# BMS_Master_RevC2.net
KiCad netlist of a schematic drawn in EAGLE
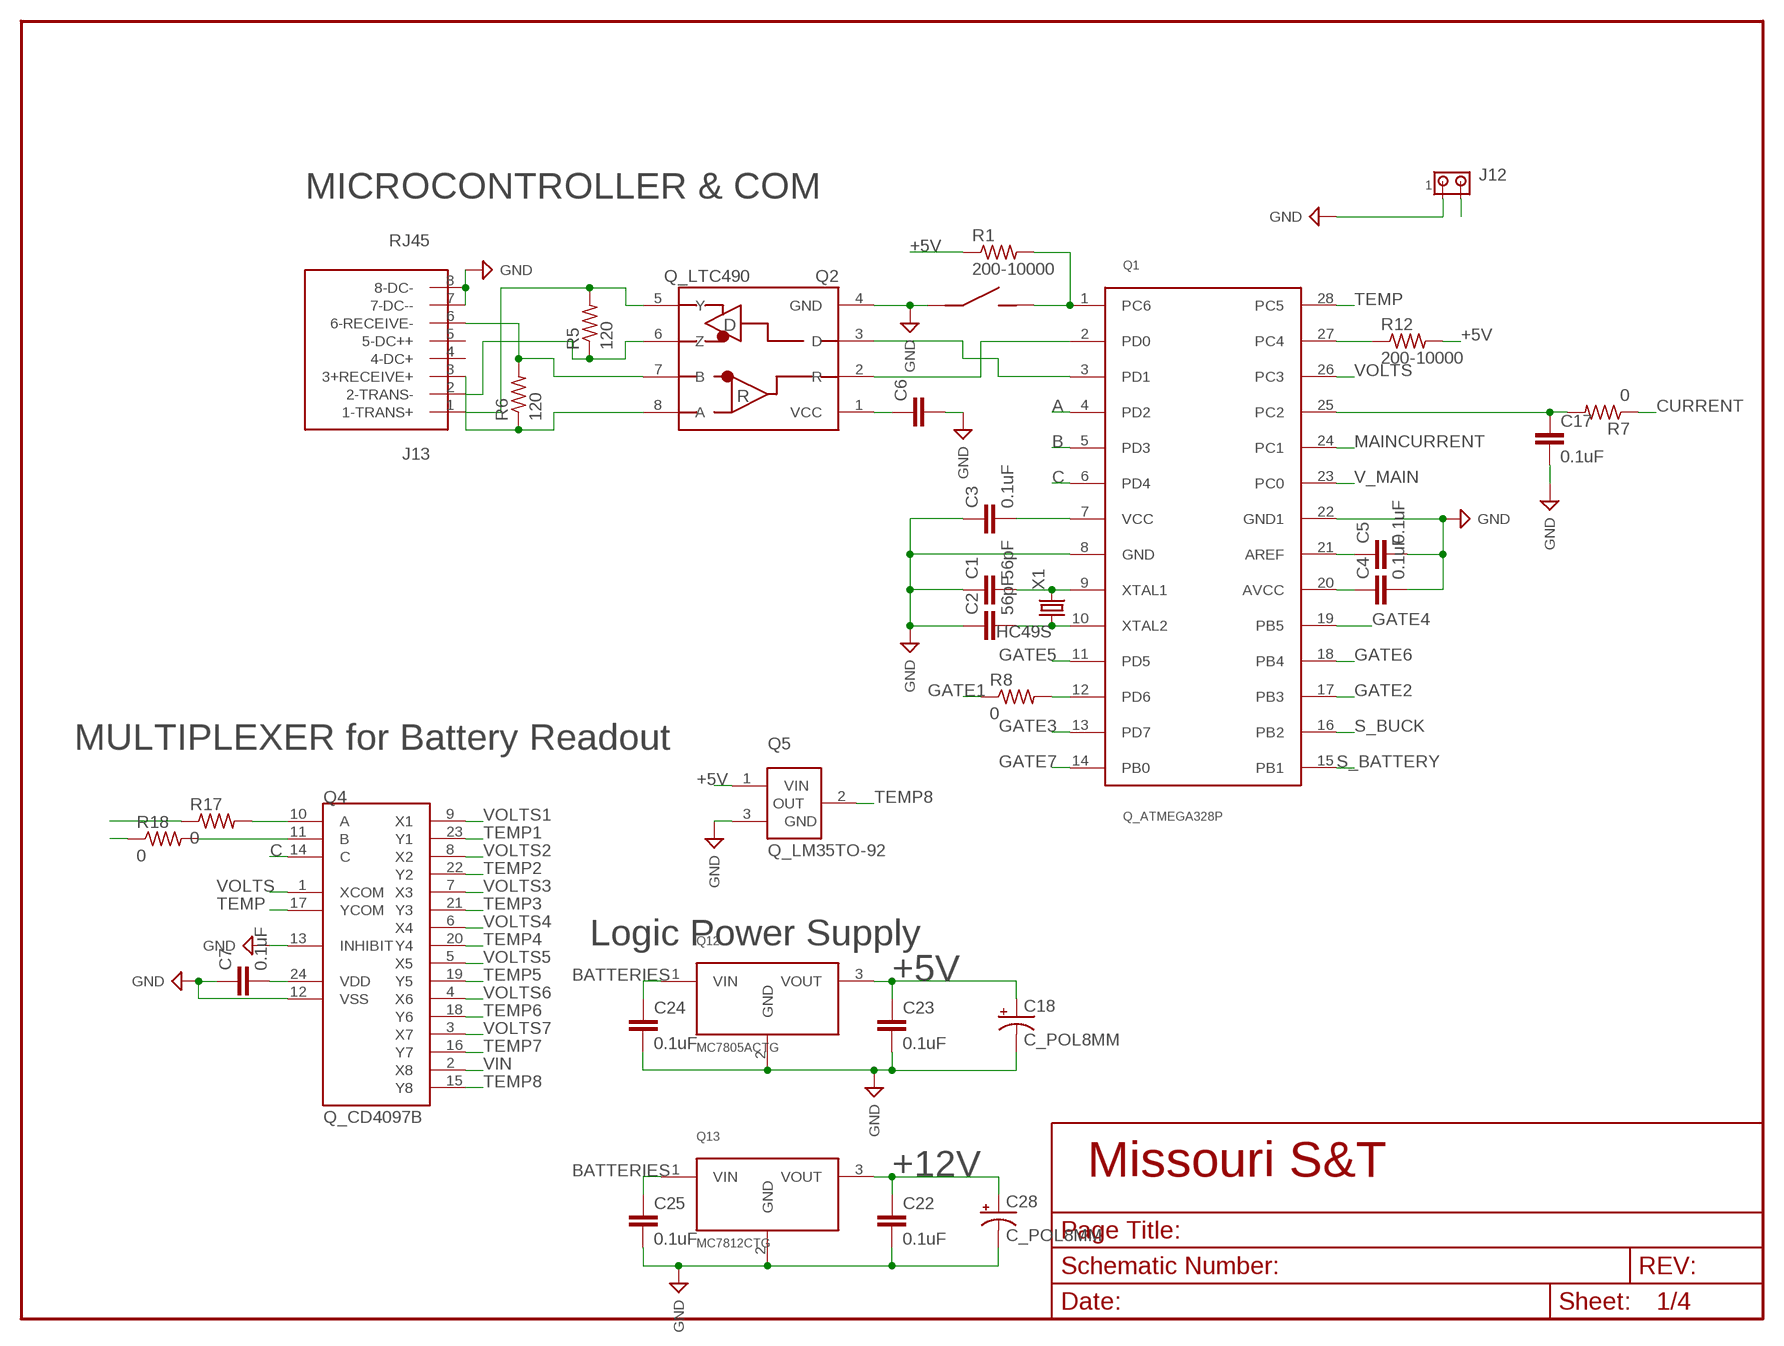
[diagram p0: schematic, sheet 1]
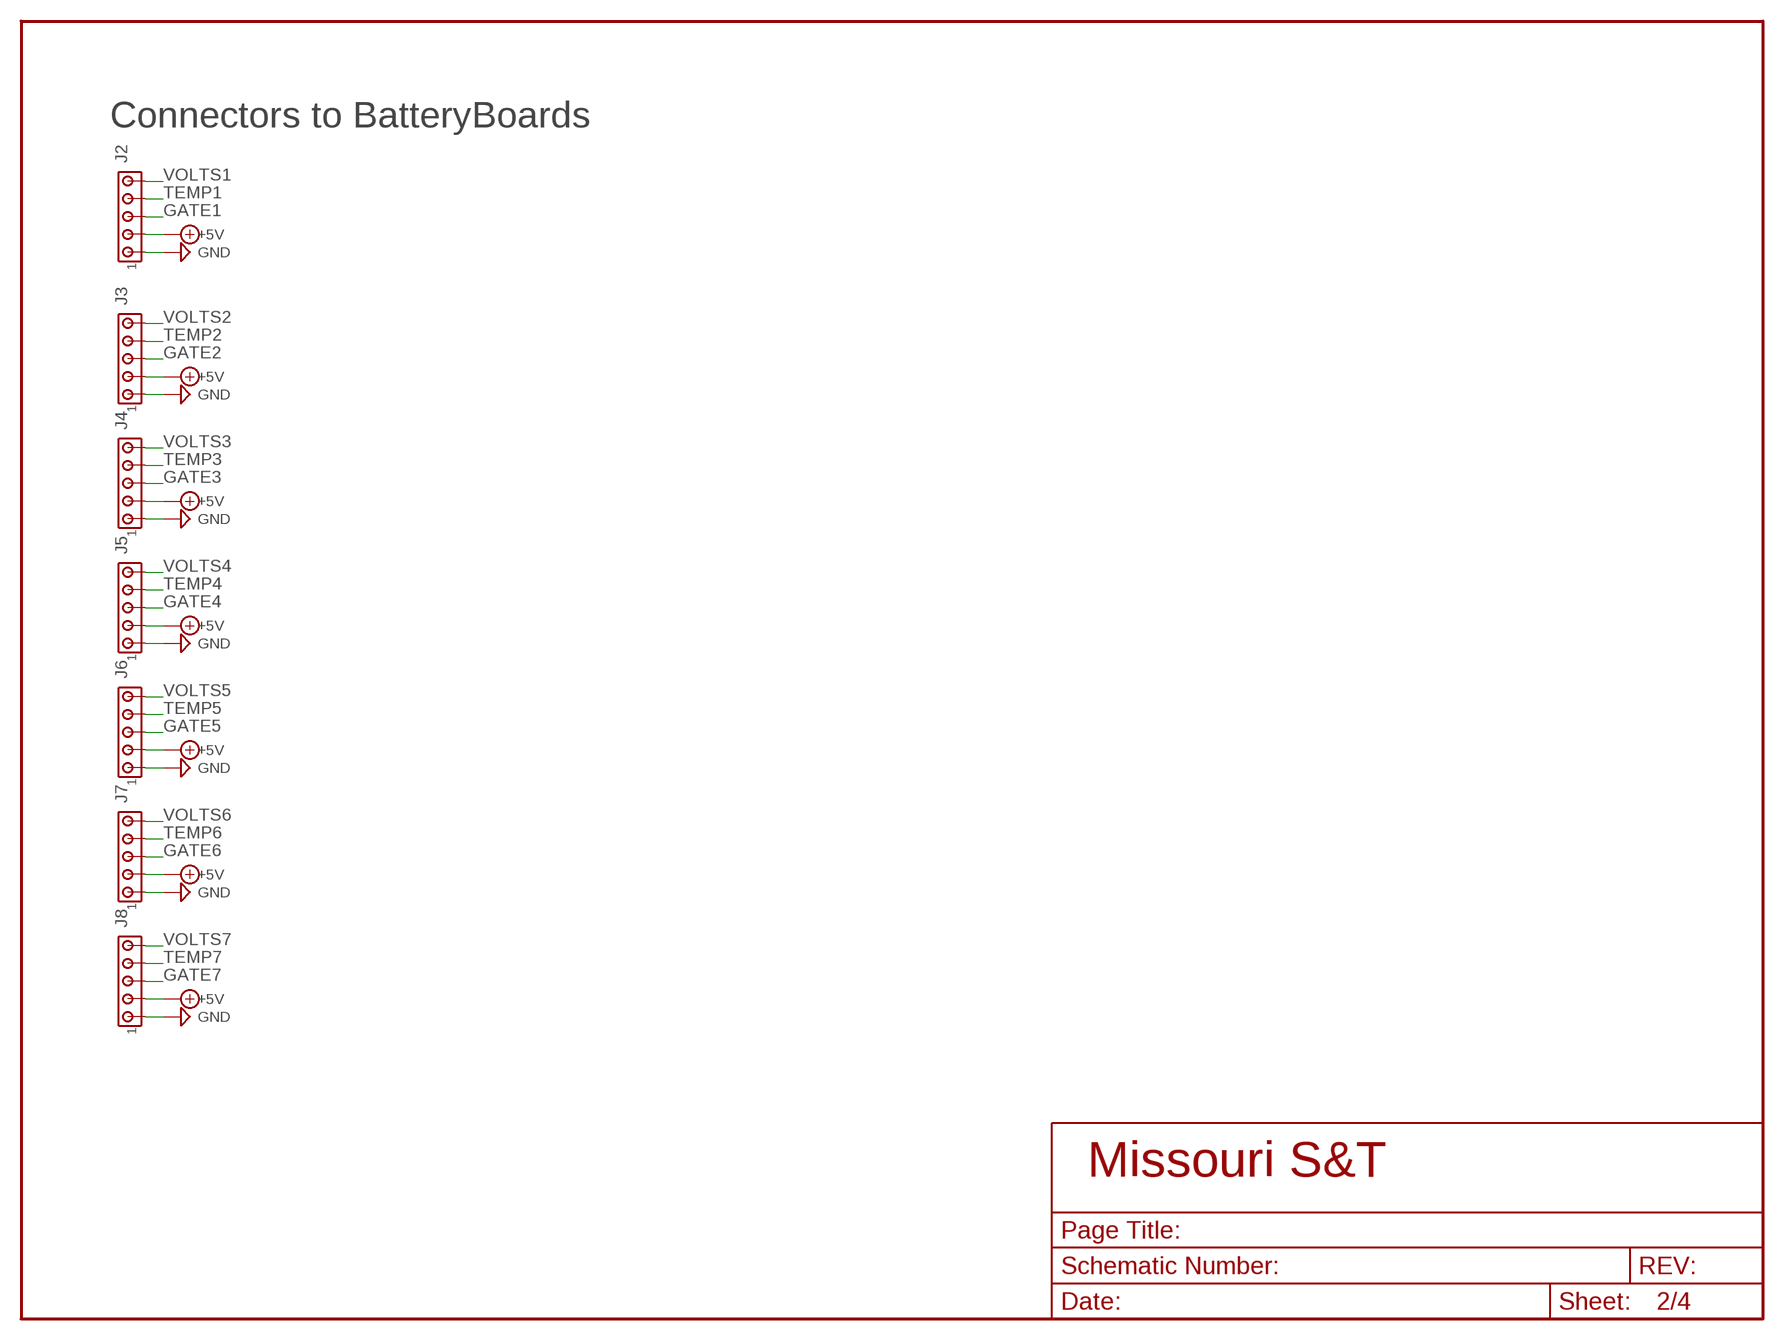
[diagram p1: schematic, sheet 2]
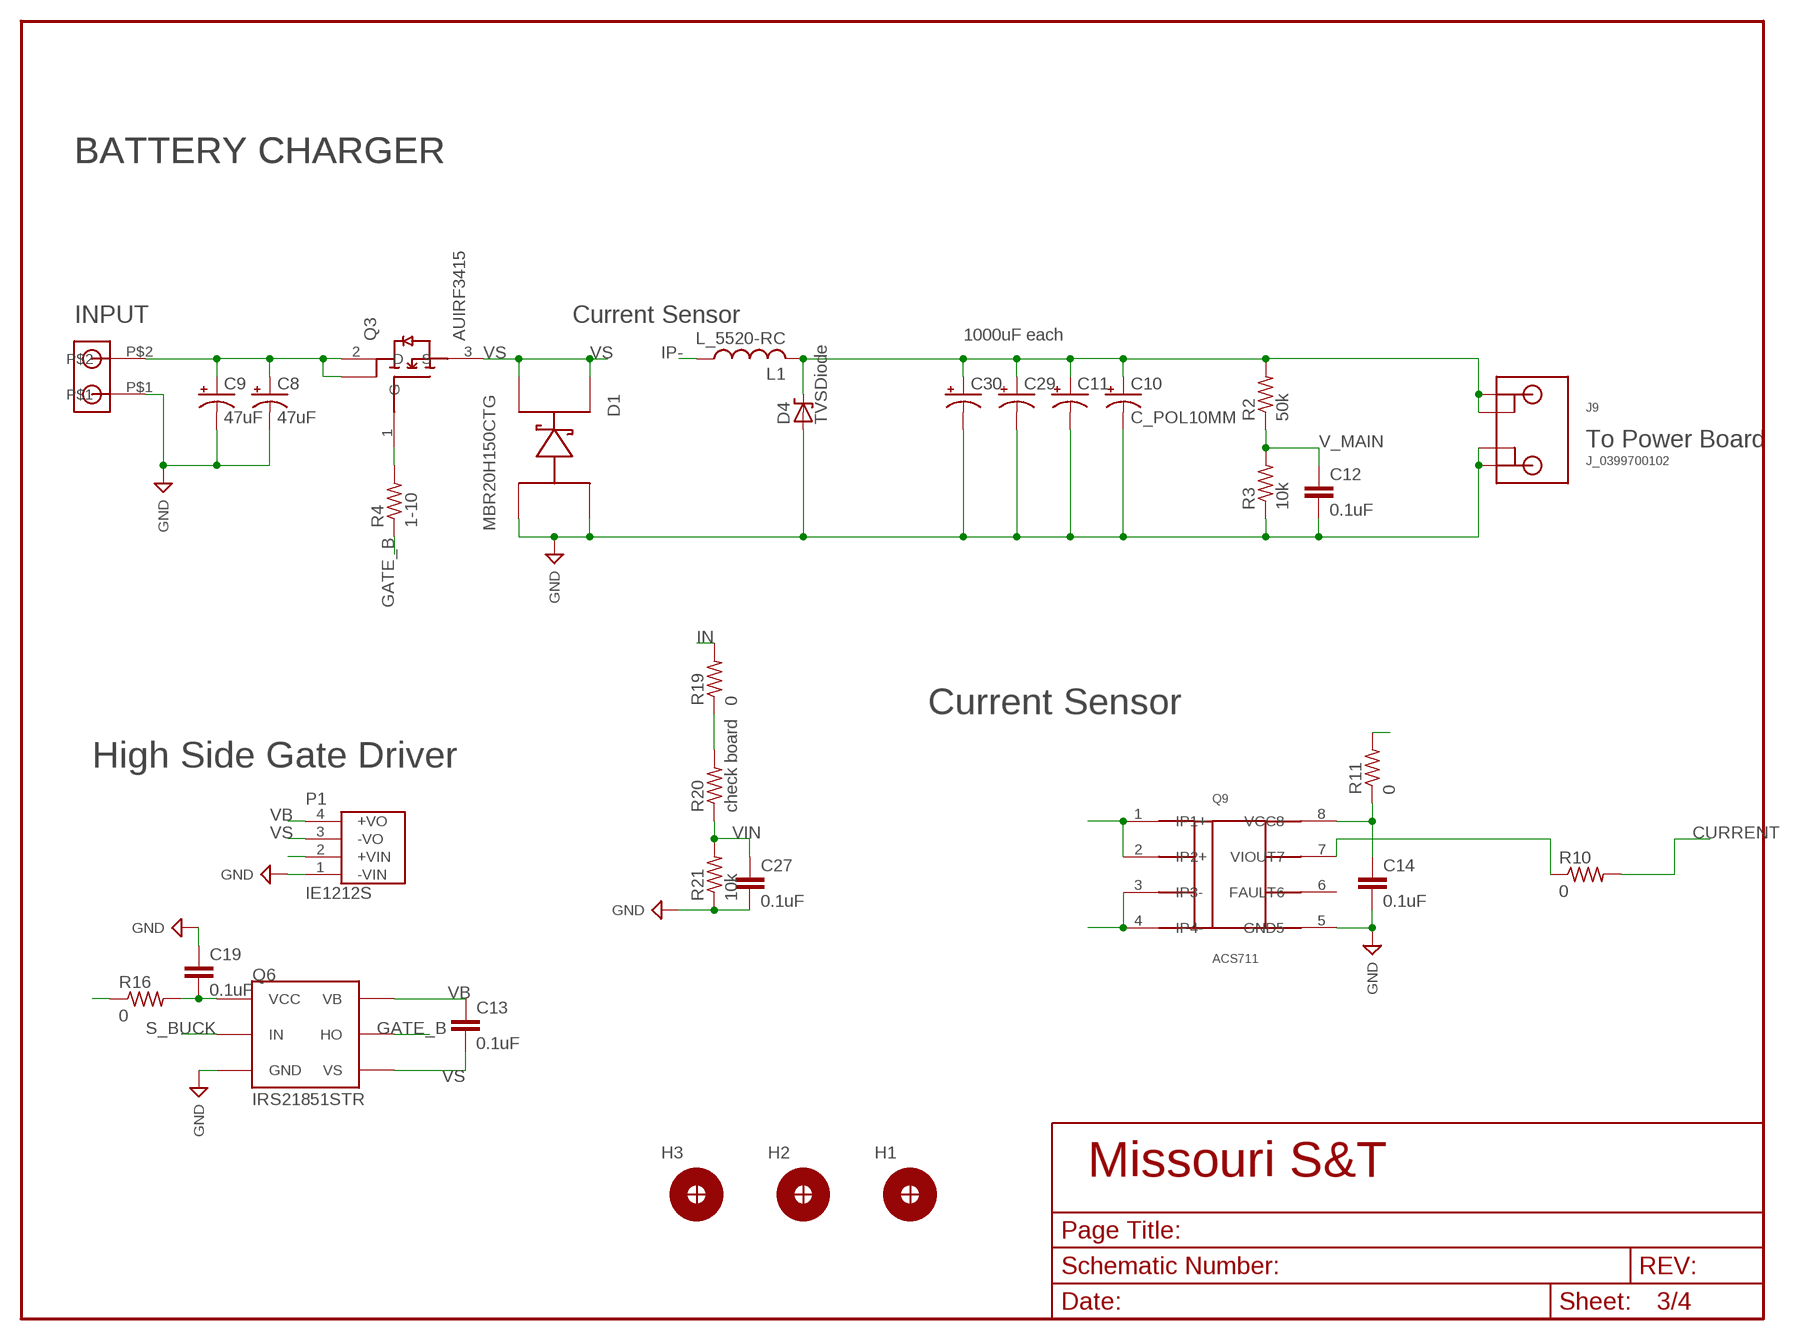
[diagram p2: schematic, sheet 3]
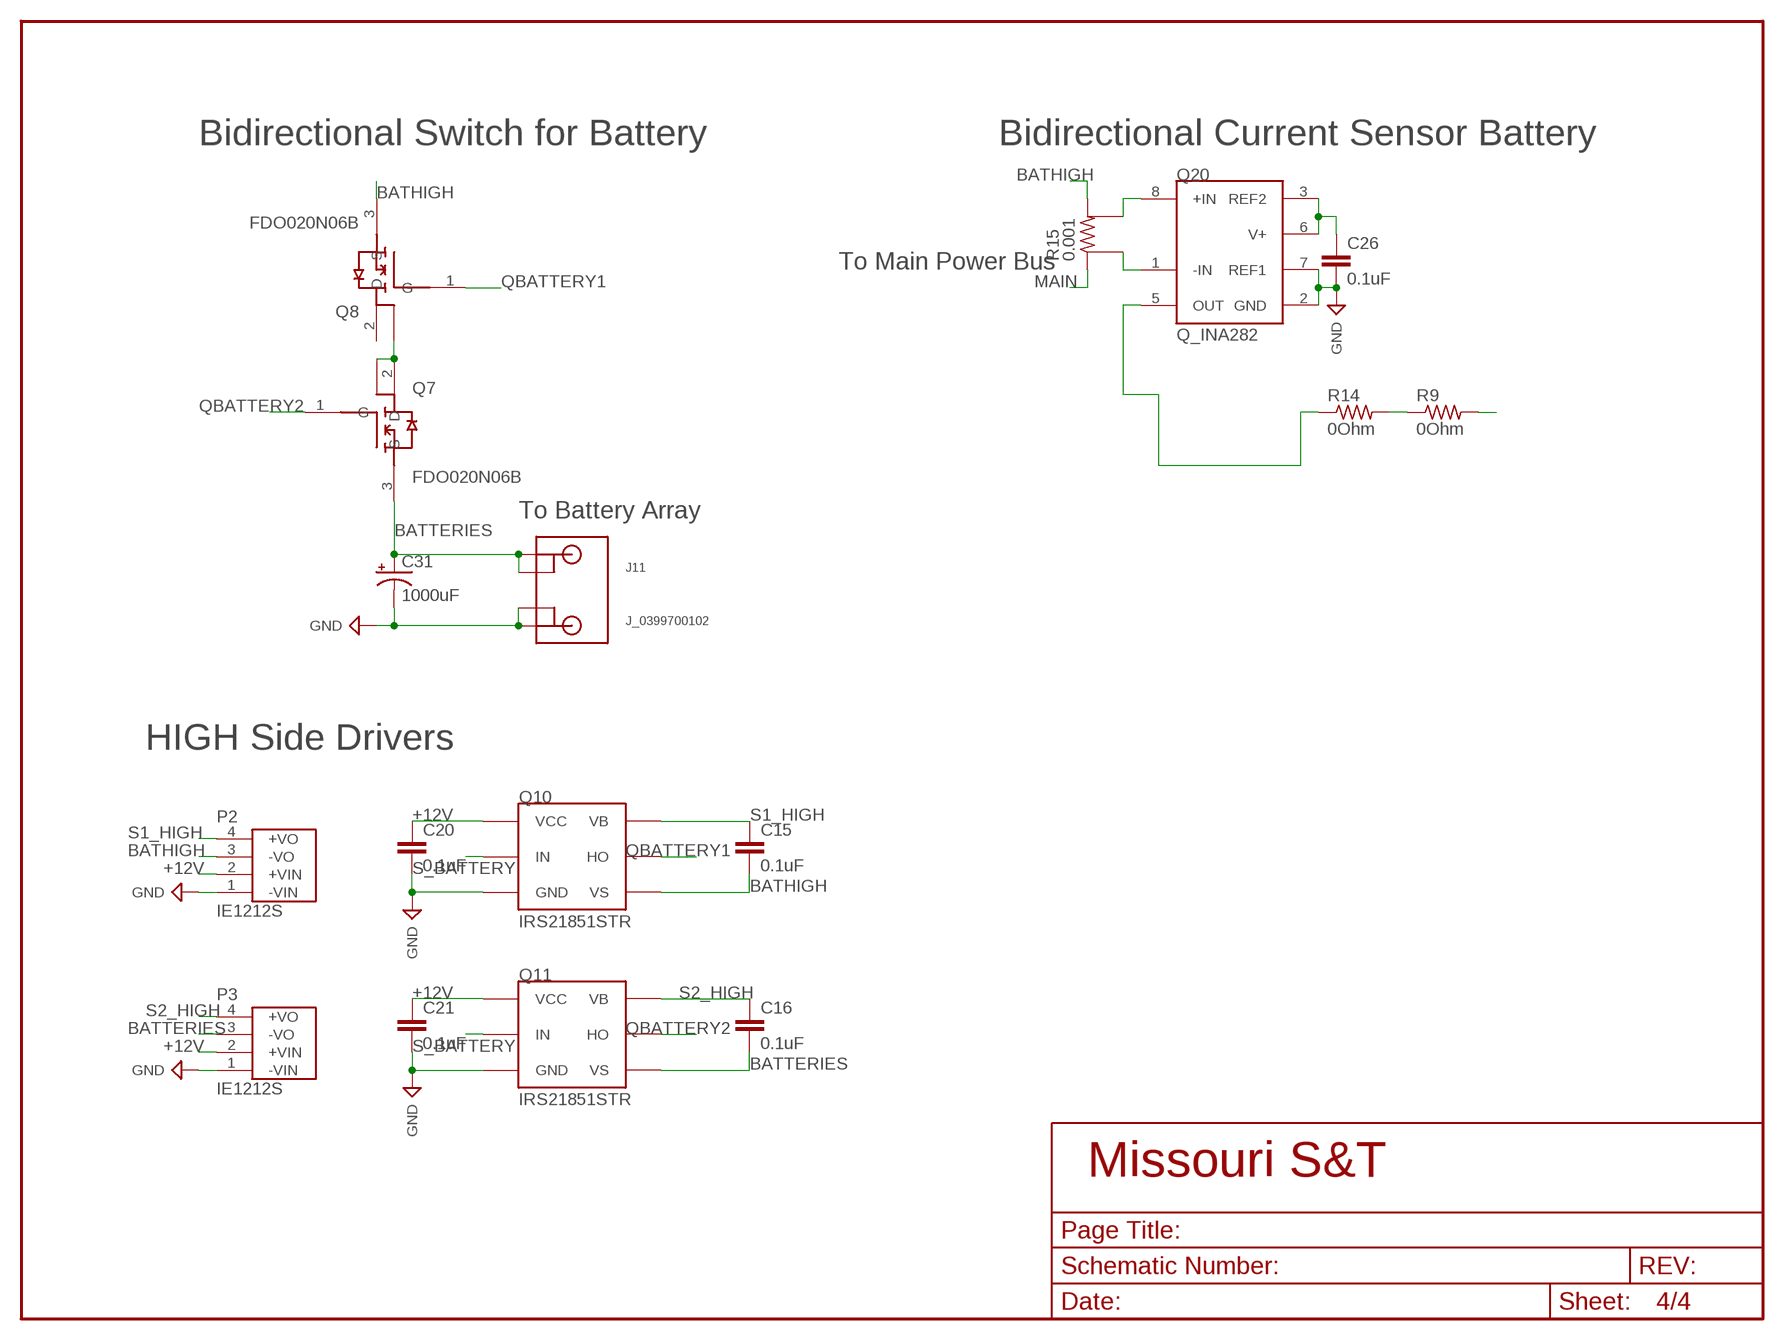
[diagram p3: schematic, sheet 4]

(export (version "E")
  (design (tool "Eeschema 10.0.6"))
  (components
    (comp (ref "J2")
      (value "J_MTA5P_100")
      (footprint "eagle-import:J_MTA100_5P")
      (libsource (lib "eagle-import") (part "J_MTA5P_100"))
    )
    (comp (ref "J3")
      (value "J_MTA5P_100")
      (footprint "eagle-import:J_MTA100_5P")
      (libsource (lib "eagle-import") (part "J_MTA5P_100"))
    )
    (comp (ref "J4")
      (value "J_MTA5P_100")
      (footprint "eagle-import:J_MTA100_5P")
      (libsource (lib "eagle-import") (part "J_MTA5P_100"))
    )
    (comp (ref "J5")
      (value "J_MTA5P_100")
      (footprint "eagle-import:J_MTA100_5P")
      (libsource (lib "eagle-import") (part "J_MTA5P_100"))
    )
    (comp (ref "J6")
      (value "J_MTA5P_100")
      (footprint "eagle-import:J_MTA100_5P")
      (libsource (lib "eagle-import") (part "J_MTA5P_100"))
    )
    (comp (ref "J7")
      (value "J_MTA5P_100")
      (footprint "eagle-import:J_MTA100_5P")
      (libsource (lib "eagle-import") (part "J_MTA5P_100"))
    )
    (comp (ref "J8")
      (value "J_MTA5P_100")
      (footprint "eagle-import:J_MTA100_5P")
      (libsource (lib "eagle-import") (part "J_MTA5P_100"))
    )
    (comp (ref "C8")
      (value "47uF")
      (footprint "eagle-import:C_10MM")
      (libsource (lib "eagle-import") (part "C_POL10MM"))
    )
    (comp (ref "C9")
      (value "47uF")
      (footprint "eagle-import:C_10MM")
      (libsource (lib "eagle-import") (part "C_POL10MM"))
    )
    (comp (ref "C10")
      (value "C_POL10MM")
      (footprint "eagle-import:C_10MM")
      (libsource (lib "eagle-import") (part "C_POL10MM"))
    )
    (comp (ref "C11")
      (value "C_POL10MM")
      (footprint "eagle-import:C_10MM")
      (libsource (lib "eagle-import") (part "C_POL10MM"))
    )
    (comp (ref "C12")
      (value "0.1uF")
      (footprint "eagle-import:C_1206")
      (libsource (lib "eagle-import") (part "C_CAP_1206"))
    )
    (comp (ref "C13")
      (value "0.1uF")
      (footprint "eagle-import:C_1206")
      (libsource (lib "eagle-import") (part "C_CAP_1206"))
    )
    (comp (ref "C14")
      (value "0.1uF")
      (footprint "eagle-import:C_1206")
      (libsource (lib "eagle-import") (part "C_CAP_1206"))
    )
    (comp (ref "C19")
      (value "0.1uF")
      (footprint "eagle-import:C_1206")
      (libsource (lib "eagle-import") (part "C_CAP_1206"))
    )
    (comp (ref "C27")
      (value "0.1uF")
      (footprint "eagle-import:C_1206")
      (libsource (lib "eagle-import") (part "C_CAP_1206"))
    )
    (comp (ref "C29")
      (value "C_POL10MM")
      (footprint "eagle-import:C_10MM")
      (libsource (lib "eagle-import") (part "C_POL10MM"))
    )
    (comp (ref "C30")
      (value "C_POL10MM")
      (footprint "eagle-import:C_10MM")
      (libsource (lib "eagle-import") (part "C_POL10MM"))
    )
    (comp (ref "D1")
      (value "MBR20H150CTG")
      (footprint "eagle-import:TO-220-FLAT")
      (libsource (lib "eagle-import") (part "D_MBR20H150CTG"))
    )
    (comp (ref "D4")
      (value "TVSDiode")
      (footprint "eagle-import:DIODE_D3.5MM_LS15.24MM")
      (libsource (lib "eagle-import") (part "D_1.5KE480A_D3.5MM_LS15.24MM"))
    )
    (comp (ref "H1")
      (value "H_MNTHOLE_#6")
      (footprint "eagle-import:H_MNTHOLE_#6")
      (libsource (lib "eagle-import") (part "H_MNTHOLE_#6"))
    )
    (comp (ref "H2")
      (value "H_MNTHOLE_#6")
      (footprint "eagle-import:H_MNTHOLE_#6")
      (libsource (lib "eagle-import") (part "H_MNTHOLE_#6"))
    )
    (comp (ref "H3")
      (value "H_MNTHOLE_#6")
      (footprint "eagle-import:H_MNTHOLE_#6")
      (libsource (lib "eagle-import") (part "H_MNTHOLE_#6"))
    )
    (comp (ref "J9")
      (value "J_0399700102")
      (footprint "eagle-import:J_2CONHC")
      (libsource (lib "eagle-import") (part "J_0399700102"))
    )
    (comp (ref "J10")
      (value "J_1546074-2")
      (footprint "eagle-import:THERM_BLOCK_2")
      (libsource (lib "eagle-import") (part "J_1546074-2"))
    )
    (comp (ref "L1")
      (value "L_5520-RC")
      (footprint "eagle-import:L_5520-RC")
      (libsource (lib "eagle-import") (part "L_5520-RC"))
    )
    (comp (ref "P1")
      (value "IE1212S")
      (footprint "eagle-import:TME1215S")
      (libsource (lib "eagle-import") (part "TME1215S"))
    )
    (comp (ref "Q3")
      (value "AUIRF3415")
      (footprint "eagle-import:TO-220-FLAT")
      (libsource (lib "eagle-import") (part "Q_CSD18532KCSPCB"))
    )
    (comp (ref "Q6")
      (value "IRS21851STR")
      (footprint "eagle-import:SOIC8")
      (libsource (lib "eagle-import") (part "Q_IRS21851STR"))
    )
    (comp (ref "Q9")
      (value "ACS711")
      (footprint "eagle-import:Q_SO8")
      (libsource (lib "eagle-import") (part "Q_SO8ACS711"))
    )
    (comp (ref "R2")
      (value "50k")
      (footprint "eagle-import:R_1_4W")
      (libsource (lib "eagle-import") (part "R_1/4W"))
    )
    (comp (ref "R3")
      (value "10k")
      (footprint "eagle-import:R_1206")
      (libsource (lib "eagle-import") (part "R_RES_1206"))
    )
    (comp (ref "R4")
      (value "1-10")
      (footprint "eagle-import:R_1206")
      (libsource (lib "eagle-import") (part "Lib_Passive - Copy_R_RES_1206"))
    )
    (comp (ref "R10")
      (value "0")
      (footprint "eagle-import:R_1_4W")
      (libsource (lib "eagle-import") (part "R_1/4W"))
    )
    (comp (ref "R11")
      (value "0")
      (footprint "eagle-import:R_1_4W")
      (libsource (lib "eagle-import") (part "R_1/4W"))
    )
    (comp (ref "R16")
      (value "0")
      (footprint "eagle-import:R_1_4W")
      (libsource (lib "eagle-import") (part "R_1/4W"))
    )
    (comp (ref "R19")
      (value "0")
      (footprint "eagle-import:R_1_4W")
      (libsource (lib "eagle-import") (part "R_1/4W"))
    )
    (comp (ref "R20")
      (value "check board")
      (footprint "eagle-import:R_1_4W")
      (libsource (lib "eagle-import") (part "R_1/4W"))
    )
    (comp (ref "R21")
      (value "10k")
      (footprint "eagle-import:R_1206")
      (libsource (lib "eagle-import") (part "R_RES_1206"))
    )
    (comp (ref "C1")
      (value "56pF")
      (footprint "eagle-import:C_1206")
      (libsource (lib "eagle-import") (part "C_CAP_1206"))
    )
    (comp (ref "C2")
      (value "56pF")
      (footprint "eagle-import:C_1206")
      (libsource (lib "eagle-import") (part "C_CAP_1206"))
    )
    (comp (ref "C3")
      (value "0.1uF")
      (footprint "eagle-import:C_1206")
      (libsource (lib "eagle-import") (part "C_CAP_1206"))
    )
    (comp (ref "C4")
      (value "0.1uF")
      (footprint "eagle-import:C_1206")
      (libsource (lib "eagle-import") (part "C_CAP_1206"))
    )
    (comp (ref "C5")
      (value "0.1uF")
      (footprint "eagle-import:C_1206")
      (libsource (lib "eagle-import") (part "C_CAP_1206"))
    )
    (comp (ref "C6")
      (value "C_CAP_1206")
      (footprint "eagle-import:C_1206")
      (libsource (lib "eagle-import") (part "C_CAP_1206"))
    )
    (comp (ref "C7")
      (value "0.1uF")
      (footprint "eagle-import:C_1206")
      (libsource (lib "eagle-import") (part "C_CAP_1206"))
    )
    (comp (ref "C17")
      (value "0.1uF")
      (footprint "eagle-import:C_1206")
      (libsource (lib "eagle-import") (part "C_CAP_1206"))
    )
    (comp (ref "C18")
      (value "C_POL8MM")
      (footprint "eagle-import:C_8MM")
      (libsource (lib "eagle-import") (part "C_POL8MM"))
    )
    (comp (ref "C22")
      (value "0.1uF")
      (footprint "eagle-import:C_1206")
      (libsource (lib "eagle-import") (part "C_CAP_1206"))
    )
    (comp (ref "C23")
      (value "0.1uF")
      (footprint "eagle-import:C_1206")
      (libsource (lib "eagle-import") (part "C_CAP_1206"))
    )
    (comp (ref "C24")
      (value "0.1uF")
      (footprint "eagle-import:C_1206")
      (libsource (lib "eagle-import") (part "C_CAP_1206"))
    )
    (comp (ref "C25")
      (value "0.1uF")
      (footprint "eagle-import:C_1206")
      (libsource (lib "eagle-import") (part "C_CAP_1206"))
    )
    (comp (ref "C28")
      (value "C_POL8MM")
      (footprint "eagle-import:C_8MM")
      (libsource (lib "eagle-import") (part "C_POL8MM"))
    )
    (comp (ref "J1")
      (value "J_MC32857")
      (footprint "eagle-import:J_TOGGLE")
      (libsource (lib "eagle-import") (part "J_MC32857"))
    )
    (comp (ref "J12")
      (value "J_MTA2P_100")
      (footprint "eagle-import:J_MTA100_2P")
      (libsource (lib "eagle-import") (part "J_MTA2P_100"))
    )
    (comp (ref "J13")
      (value "RJ45")
      (footprint "eagle-import:RJ45-CAT5E")
      (libsource (lib "eagle-import") (part "RJ45"))
    )
    (comp (ref "Q1")
      (value "Q_ATMEGA328P")
      (footprint "eagle-import:DIP28")
      (libsource (lib "eagle-import") (part "Q_ATMEGA328P"))
    )
    (comp (ref "Q2")
      (value "Q_LTC490")
      (footprint "eagle-import:DIP8")
      (libsource (lib "eagle-import") (part "Q_LTC490"))
    )
    (comp (ref "Q4")
      (value "Q_CD4097B")
      (footprint "eagle-import:WDIP24")
      (libsource (lib "eagle-import") (part "Q_CD4067BRIGHT"))
    )
    (comp (ref "Q5")
      (value "Q_LM35TO-92")
      (footprint "eagle-import:TO-92-3")
      (libsource (lib "eagle-import") (part "Q_LM35TO-92"))
    )
    (comp (ref "Q12")
      (value "MC7805ACTG")
      (footprint "eagle-import:TO-220")
      (libsource (lib "eagle-import") (part "Q_LDO"))
    )
    (comp (ref "Q13")
      (value "MC7812CTG")
      (footprint "eagle-import:TO-220")
      (libsource (lib "eagle-import") (part "Q_LDO"))
    )
    (comp (ref "R1")
      (value "200-10000")
      (footprint "eagle-import:R_1206")
      (libsource (lib "eagle-import") (part "R_RES_1206"))
    )
    (comp (ref "R5")
      (value "120")
      (footprint "eagle-import:R_1206")
      (libsource (lib "eagle-import") (part "Lib_Passive - Copy_R_RES_1206"))
    )
    (comp (ref "R6")
      (value "120")
      (footprint "eagle-import:R_1206")
      (libsource (lib "eagle-import") (part "Lib_Passive - Copy_R_RES_1206"))
    )
    (comp (ref "R7")
      (value "0")
      (footprint "eagle-import:R_1_4W")
      (libsource (lib "eagle-import") (part "R_1/4W"))
    )
    (comp (ref "R8")
      (value "0")
      (footprint "eagle-import:R_1_4W")
      (libsource (lib "eagle-import") (part "R_1/4W"))
    )
    (comp (ref "R12")
      (value "200-10000")
      (footprint "eagle-import:R_0805")
      (libsource (lib "eagle-import") (part "R_RES_0805"))
    )
    (comp (ref "R17")
      (value "0")
      (footprint "eagle-import:R_1_4W")
      (libsource (lib "eagle-import") (part "R_1/4W"))
    )
    (comp (ref "R18")
      (value "0")
      (footprint "eagle-import:R_1_4W")
      (libsource (lib "eagle-import") (part "R_1/4W"))
    )
    (comp (ref "X1")
      (value "HC49S")
      (footprint "eagle-import:HC-49")
      (libsource (lib "eagle-import") (part "X_HC49SCRYSTAL"))
    )
    (comp (ref "C15")
      (value "0.1uF")
      (footprint "eagle-import:C_1206")
      (libsource (lib "eagle-import") (part "C_CAP_1206"))
    )
    (comp (ref "C16")
      (value "0.1uF")
      (footprint "eagle-import:C_1206")
      (libsource (lib "eagle-import") (part "C_CAP_1206"))
    )
    (comp (ref "C20")
      (value "0.1uF")
      (footprint "eagle-import:C_1206")
      (libsource (lib "eagle-import") (part "C_CAP_1206"))
    )
    (comp (ref "C21")
      (value "0.1uF")
      (footprint "eagle-import:C_1206")
      (libsource (lib "eagle-import") (part "C_CAP_1206"))
    )
    (comp (ref "C26")
      (value "0.1uF")
      (footprint "eagle-import:C_1206")
      (libsource (lib "eagle-import") (part "C_CAP_1206"))
    )
    (comp (ref "C31")
      (value "1000uF")
      (footprint "eagle-import:C_10MM")
      (libsource (lib "eagle-import") (part "C_POL10MM"))
    )
    (comp (ref "J11")
      (value "J_0399700102")
      (footprint "eagle-import:J_2CONHC")
      (libsource (lib "eagle-import") (part "J_0399700102"))
    )
    (comp (ref "P2")
      (value "IE1212S")
      (footprint "eagle-import:TME1215S")
      (libsource (lib "eagle-import") (part "TME1215S"))
    )
    (comp (ref "P3")
      (value "IE1212S")
      (footprint "eagle-import:TME1215S")
      (libsource (lib "eagle-import") (part "TME1215S"))
    )
    (comp (ref "Q7")
      (value "FDO020N06B")
      (footprint "eagle-import:TO-220-FLAT")
      (libsource (lib "eagle-import") (part "Q_CSD18532KCSPCB"))
    )
    (comp (ref "Q8")
      (value "FDO020N06B")
      (footprint "eagle-import:TO-220-FLAT")
      (libsource (lib "eagle-import") (part "Q_CSD18532KCSPCB"))
    )
    (comp (ref "Q10")
      (value "IRS21851STR")
      (footprint "eagle-import:SOIC8")
      (libsource (lib "eagle-import") (part "Q_IRS21851STR"))
    )
    (comp (ref "Q11")
      (value "IRS21851STR")
      (footprint "eagle-import:SOIC8")
      (libsource (lib "eagle-import") (part "Q_IRS21851STR"))
    )
    (comp (ref "Q20")
      (value "Q_INA282")
      (footprint "eagle-import:SOIC8")
      (libsource (lib "eagle-import") (part "Q_INA28"))
    )
    (comp (ref "R9")
      (value "0Ohm")
      (footprint "eagle-import:R_1_4W")
      (libsource (lib "eagle-import") (part "R_1/4W"))
    )
    (comp (ref "R14")
      (value "0Ohm")
      (footprint "eagle-import:R_1_4W")
      (libsource (lib "eagle-import") (part "R_1/4W"))
    )
    (comp (ref "R15")
      (value "0.001")
      (footprint "eagle-import:R_FC4L")
      (libsource (lib "eagle-import") (part "R_FC4L110R001JER"))
    )
  )
  (nets
    (net (code "1") (name "+5V") (class "Default")
      (node (ref "C18") (pin "+") (pinfunction "+_+") (pintype "passive"))
      (node (ref "C23") (pin "1") (pinfunction "1_1") (pintype "passive"))
      (node (ref "C3") (pin "2") (pinfunction "2_2") (pintype "passive"))
      (node (ref "C4") (pin "1") (pinfunction "1_1") (pintype "passive"))
      (node (ref "C6") (pin "1") (pinfunction "1_1") (pintype "passive"))
      (node (ref "C7") (pin "2") (pinfunction "2_2") (pintype "passive"))
      (node (ref "J2") (pin "2") (pinfunction "2_2") (pintype "passive"))
      (node (ref "J3") (pin "2") (pinfunction "2_2") (pintype "passive"))
      (node (ref "J4") (pin "2") (pinfunction "2_2") (pintype "passive"))
      (node (ref "J5") (pin "2") (pinfunction "2_2") (pintype "passive"))
      (node (ref "J6") (pin "2") (pinfunction "2_2") (pintype "passive"))
      (node (ref "J7") (pin "2") (pinfunction "2_2") (pintype "passive"))
      (node (ref "J8") (pin "2") (pinfunction "2_2") (pintype "passive"))
      (node (ref "Q1") (pin "20") (pinfunction "AVCC_20") (pintype "bidirectional"))
      (node (ref "Q1") (pin "7") (pinfunction "VCC_7") (pintype "bidirectional"))
      (node (ref "Q12") (pin "3") (pinfunction "VOUT_3") (pintype "bidirectional"))
      (node (ref "Q2") (pin "1") (pinfunction "VCC_1") (pintype "bidirectional"))
      (node (ref "Q4") (pin "24") (pinfunction "VDD_24") (pintype "bidirectional"))
      (node (ref "Q5") (pin "1") (pinfunction "VIN_1") (pintype "bidirectional"))
      (node (ref "R1") (pin "1") (pinfunction "1_1") (pintype "passive"))
      (node (ref "R11") (pin "2") (pinfunction "2_2") (pintype "passive"))
      (node (ref "R12") (pin "2") (pinfunction "2_2") (pintype "passive"))
    )
    (net (code "2") (name "+5V1") (class "Default")
      (node (ref "C14") (pin "1") (pinfunction "1_1") (pintype "passive"))
      (node (ref "C26") (pin "1") (pinfunction "1_1") (pintype "passive"))
      (node (ref "Q20") (pin "3") (pinfunction "REF2_3") (pintype "bidirectional"))
      (node (ref "Q20") (pin "6") (pinfunction "V+_6") (pintype "bidirectional"))
      (node (ref "Q9") (pin "8") (pinfunction "VCC8_8") (pintype "bidirectional"))
      (node (ref "R11") (pin "1") (pinfunction "1_1") (pintype "passive"))
    )
    (net (code "3") (name "+12V") (class "Default")
      (node (ref "C20") (pin "1") (pinfunction "1_1") (pintype "passive"))
      (node (ref "C21") (pin "1") (pinfunction "1_1") (pintype "passive"))
      (node (ref "C22") (pin "1") (pinfunction "1_1") (pintype "passive"))
      (node (ref "C28") (pin "+") (pinfunction "+_+") (pintype "passive"))
      (node (ref "P2") (pin "2") (pinfunction "+VIN_2") (pintype "input"))
      (node (ref "P3") (pin "2") (pinfunction "+VIN_2") (pintype "input"))
      (node (ref "Q10") (pin "1") (pinfunction "VCC_1") (pintype "bidirectional"))
      (node (ref "Q11") (pin "1") (pinfunction "VCC_1") (pintype "bidirectional"))
      (node (ref "Q13") (pin "3") (pinfunction "VOUT_3") (pintype "bidirectional"))
      (node (ref "R16") (pin "1") (pinfunction "1_1") (pintype "passive"))
    )
    (net (code "4") (name "+12V1") (class "Default")
      (node (ref "C19") (pin "2") (pinfunction "2_2") (pintype "passive"))
      (node (ref "P1") (pin "2") (pinfunction "+VIN_2") (pintype "input"))
      (node (ref "Q6") (pin "1") (pinfunction "VCC_1") (pintype "bidirectional"))
      (node (ref "R16") (pin "2") (pinfunction "2_2") (pintype "passive"))
    )
    (net (code "5") (name "A") (class "Default")
      (node (ref "Q1") (pin "4") (pinfunction "PD2_4") (pintype "bidirectional"))
      (node (ref "R17") (pin "1") (pinfunction "1_1") (pintype "passive"))
    )
    (net (code "6") (name "B") (class "Default")
      (node (ref "Q1") (pin "5") (pinfunction "PD3_5") (pintype "bidirectional"))
      (node (ref "R18") (pin "1") (pinfunction "1_1") (pintype "passive"))
    )
    (net (code "7") (name "BATHIGH") (class "Default")
      (node (ref "C15") (pin "2") (pinfunction "2_2") (pintype "passive"))
      (node (ref "P2") (pin "3") (pinfunction "-VO_3") (pintype "output"))
      (node (ref "Q10") (pin "6") (pinfunction "VS_6") (pintype "bidirectional"))
      (node (ref "Q8") (pin "3") (pinfunction "S_3") (pintype "bidirectional"))
      (node (ref "R15") (pin "2") (pinfunction "2_2") (pintype "passive"))
    )
    (net (code "8") (name "BATTERIES") (class "Default")
      (node (ref "C16") (pin "2") (pinfunction "2_2") (pintype "passive"))
      (node (ref "C24") (pin "1") (pinfunction "1_1") (pintype "passive"))
      (node (ref "C25") (pin "1") (pinfunction "1_1") (pintype "passive"))
      (node (ref "C31") (pin "P$1") (pinfunction "+_P$1") (pintype "passive"))
      (node (ref "J11") (pin "PIN1-1") (pinfunction "1-1_PIN1-1") (pintype "bidirectional"))
      (node (ref "J11") (pin "PIN1-2") (pinfunction "1-2_PIN1-2") (pintype "bidirectional"))
      (node (ref "P3") (pin "3") (pinfunction "-VO_3") (pintype "output"))
      (node (ref "Q11") (pin "6") (pinfunction "VS_6") (pintype "bidirectional"))
      (node (ref "Q12") (pin "1") (pinfunction "VIN_1") (pintype "bidirectional"))
      (node (ref "Q13") (pin "1") (pinfunction "VIN_1") (pintype "bidirectional"))
      (node (ref "Q7") (pin "3") (pinfunction "S_3") (pintype "bidirectional"))
    )
    (net (code "9") (name "C") (class "Default")
      (node (ref "Q1") (pin "6") (pinfunction "PD4_6") (pintype "bidirectional"))
      (node (ref "Q4") (pin "14") (pinfunction "C_14") (pintype "bidirectional"))
    )
    (net (code "10") (name "CURRENT") (class "Default")
      (node (ref "R10") (pin "2") (pinfunction "2_2") (pintype "passive"))
      (node (ref "R7") (pin "1") (pinfunction "1_1") (pintype "passive"))
    )
    (net (code "11") (name "GATE1") (class "Default")
      (node (ref "J2") (pin "3") (pinfunction "3_3") (pintype "passive"))
      (node (ref "R8") (pin "1") (pinfunction "1_1") (pintype "passive"))
    )
    (net (code "12") (name "GATE2") (class "Default")
      (node (ref "J3") (pin "3") (pinfunction "3_3") (pintype "passive"))
      (node (ref "Q1") (pin "17") (pinfunction "PB3_17") (pintype "bidirectional"))
    )
    (net (code "13") (name "GATE3") (class "Default")
      (node (ref "J4") (pin "3") (pinfunction "3_3") (pintype "passive"))
      (node (ref "Q1") (pin "13") (pinfunction "PD7_13") (pintype "bidirectional"))
    )
    (net (code "14") (name "GATE4") (class "Default")
      (node (ref "J5") (pin "3") (pinfunction "3_3") (pintype "passive"))
      (node (ref "Q1") (pin "19") (pinfunction "PB5_19") (pintype "bidirectional"))
    )
    (net (code "15") (name "GATE5") (class "Default")
      (node (ref "J6") (pin "3") (pinfunction "3_3") (pintype "passive"))
      (node (ref "Q1") (pin "11") (pinfunction "PD5_11") (pintype "bidirectional"))
    )
    (net (code "16") (name "GATE6") (class "Default")
      (node (ref "J7") (pin "3") (pinfunction "3_3") (pintype "passive"))
      (node (ref "Q1") (pin "18") (pinfunction "PB4_18") (pintype "bidirectional"))
    )
    (net (code "17") (name "GATE7") (class "Default")
      (node (ref "J8") (pin "3") (pinfunction "3_3") (pintype "passive"))
      (node (ref "Q1") (pin "14") (pinfunction "PB0_14") (pintype "bidirectional"))
    )
    (net (code "18") (name "GATE_B") (class "Default")
      (node (ref "Q6") (pin "7") (pinfunction "HO_7") (pintype "bidirectional"))
      (node (ref "R4") (pin "1") (pinfunction "1_1") (pintype "passive"))
    )
    (net (code "19") (name "GND") (class "Default")
      (node (ref "C1") (pin "1") (pinfunction "1_1") (pintype "passive"))
      (node (ref "C10") (pin "P$2") (pinfunction "-_P$2") (pintype "passive"))
      (node (ref "C11") (pin "P$2") (pinfunction "-_P$2") (pintype "passive"))
      (node (ref "C12") (pin "2") (pinfunction "2_2") (pintype "passive"))
      (node (ref "C14") (pin "2") (pinfunction "2_2") (pintype "passive"))
      (node (ref "C17") (pin "2") (pinfunction "2_2") (pintype "passive"))
      (node (ref "C18") (pin "-") (pinfunction "-_-") (pintype "passive"))
      (node (ref "C19") (pin "1") (pinfunction "1_1") (pintype "passive"))
      (node (ref "C2") (pin "1") (pinfunction "1_1") (pintype "passive"))
      (node (ref "C20") (pin "2") (pinfunction "2_2") (pintype "passive"))
      (node (ref "C21") (pin "2") (pinfunction "2_2") (pintype "passive"))
      (node (ref "C22") (pin "2") (pinfunction "2_2") (pintype "passive"))
      (node (ref "C23") (pin "2") (pinfunction "2_2") (pintype "passive"))
      (node (ref "C24") (pin "2") (pinfunction "2_2") (pintype "passive"))
      (node (ref "C25") (pin "2") (pinfunction "2_2") (pintype "passive"))
      (node (ref "C26") (pin "2") (pinfunction "2_2") (pintype "passive"))
      (node (ref "C27") (pin "2") (pinfunction "2_2") (pintype "passive"))
      (node (ref "C28") (pin "-") (pinfunction "-_-") (pintype "passive"))
      (node (ref "C29") (pin "P$2") (pinfunction "-_P$2") (pintype "passive"))
      (node (ref "C3") (pin "1") (pinfunction "1_1") (pintype "passive"))
      (node (ref "C30") (pin "P$2") (pinfunction "-_P$2") (pintype "passive"))
      (node (ref "C31") (pin "P$2") (pinfunction "-_P$2") (pintype "passive"))
      (node (ref "C4") (pin "2") (pinfunction "2_2") (pintype "passive"))
      (node (ref "C5") (pin "2") (pinfunction "2_2") (pintype "passive"))
      (node (ref "C6") (pin "2") (pinfunction "2_2") (pintype "passive"))
      (node (ref "C7") (pin "1") (pinfunction "1_1") (pintype "passive"))
      (node (ref "C8") (pin "P$2") (pinfunction "-_P$2") (pintype "passive"))
      (node (ref "C9") (pin "P$2") (pinfunction "-_P$2") (pintype "passive"))
      (node (ref "D1") (pin "1") (pinfunction "A1_1") (pintype "bidirectional"))
      (node (ref "D1") (pin "3") (pinfunction "A2_3") (pintype "bidirectional"))
      (node (ref "D4") (pin "A") (pinfunction "A_A") (pintype "passive"))
      (node (ref "J1") (pin "P$1") (pinfunction "1_P$1") (pintype "bidirectional"))
      (node (ref "J10") (pin "P$1") (pinfunction "P$1_P$1") (pintype "bidirectional"))
      (node (ref "J11") (pin "PIN2-1") (pinfunction "2-1_PIN2-1") (pintype "bidirectional"))
      (node (ref "J11") (pin "PIN2-2") (pinfunction "2-2_PIN2-2") (pintype "bidirectional"))
      (node (ref "J12") (pin "1") (pinfunction "1_1") (pintype "passive"))
      (node (ref "J13") (pin "7") (pinfunction "7-DC--_7") (pintype "bidirectional"))
      (node (ref "J13") (pin "8") (pinfunction "8-DC-_8") (pintype "bidirectional"))
      (node (ref "J2") (pin "1") (pinfunction "1_1") (pintype "passive"))
      (node (ref "J3") (pin "1") (pinfunction "1_1") (pintype "passive"))
      (node (ref "J4") (pin "1") (pinfunction "1_1") (pintype "passive"))
      (node (ref "J5") (pin "1") (pinfunction "1_1") (pintype "passive"))
      (node (ref "J6") (pin "1") (pinfunction "1_1") (pintype "passive"))
      (node (ref "J7") (pin "1") (pinfunction "1_1") (pintype "passive"))
      (node (ref "J8") (pin "1") (pinfunction "1_1") (pintype "passive"))
      (node (ref "J9") (pin "PIN2-1") (pinfunction "2-1_PIN2-1") (pintype "bidirectional"))
      (node (ref "J9") (pin "PIN2-2") (pinfunction "2-2_PIN2-2") (pintype "bidirectional"))
      (node (ref "P1") (pin "1") (pinfunction "-VIN_1") (pintype "input"))
      (node (ref "P2") (pin "1") (pinfunction "-VIN_1") (pintype "input"))
      (node (ref "P3") (pin "1") (pinfunction "-VIN_1") (pintype "input"))
      (node (ref "Q1") (pin "22") (pinfunction "GND1_22") (pintype "bidirectional"))
      (node (ref "Q1") (pin "8") (pinfunction "GND_8") (pintype "bidirectional"))
      (node (ref "Q10") (pin "4") (pinfunction "GND_4") (pintype "bidirectional"))
      (node (ref "Q11") (pin "4") (pinfunction "GND_4") (pintype "bidirectional"))
      (node (ref "Q12") (pin "2") (pinfunction "GND_2") (pintype "bidirectional"))
      (node (ref "Q13") (pin "2") (pinfunction "GND_2") (pintype "bidirectional"))
      (node (ref "Q2") (pin "4") (pinfunction "GND_4") (pintype "bidirectional"))
      (node (ref "Q20") (pin "2") (pinfunction "GND_2") (pintype "bidirectional"))
      (node (ref "Q20") (pin "7") (pinfunction "REF1_7") (pintype "bidirectional"))
      (node (ref "Q4") (pin "12") (pinfunction "VSS_12") (pintype "bidirectional"))
      (node (ref "Q4") (pin "13") (pinfunction "INHIBIT_13") (pintype "bidirectional"))
      (node (ref "Q5") (pin "3") (pinfunction "GND_3") (pintype "bidirectional"))
      (node (ref "Q6") (pin "4") (pinfunction "GND_4") (pintype "bidirectional"))
      (node (ref "Q9") (pin "5") (pinfunction "GND5_5") (pintype "bidirectional"))
      (node (ref "R21") (pin "1") (pinfunction "1_1") (pintype "passive"))
      (node (ref "R3") (pin "1") (pinfunction "1_1") (pintype "passive"))
    )
    (net (code "20") (name "IN") (class "Default")
      (node (ref "C8") (pin "P$1") (pinfunction "+_P$1") (pintype "passive"))
      (node (ref "C9") (pin "P$1") (pinfunction "+_P$1") (pintype "passive"))
      (node (ref "J10") (pin "P$2") (pinfunction "P$2_P$2") (pintype "bidirectional"))
      (node (ref "Q3") (pin "2") (pinfunction "D_2") (pintype "bidirectional"))
      (node (ref "Q3") (pin "4") (pinfunction "P$1_4") (pintype "bidirectional"))
      (node (ref "R19") (pin "2") (pinfunction "2_2") (pintype "passive"))
    )
    (net (code "21") (name "IP-") (class "Default")
      (node (ref "L1") (pin "1") (pinfunction "1_1") (pintype "passive"))
      (node (ref "Q9") (pin "1") (pinfunction "IP1+_1") (pintype "bidirectional"))
      (node (ref "Q9") (pin "2") (pinfunction "IP2+_2") (pintype "bidirectional"))
    )
    (net (code "22") (name "MAIN") (class "Default")
      (node (ref "C10") (pin "P$1") (pinfunction "+_P$1") (pintype "passive"))
      (node (ref "C11") (pin "P$1") (pinfunction "+_P$1") (pintype "passive"))
      (node (ref "C29") (pin "P$1") (pinfunction "+_P$1") (pintype "passive"))
      (node (ref "C30") (pin "P$1") (pinfunction "+_P$1") (pintype "passive"))
      (node (ref "D4") (pin "C") (pinfunction "K_C") (pintype "passive"))
      (node (ref "J9") (pin "PIN1-1") (pinfunction "1-1_PIN1-1") (pintype "bidirectional"))
      (node (ref "J9") (pin "PIN1-2") (pinfunction "1-2_PIN1-2") (pintype "bidirectional"))
      (node (ref "L1") (pin "2") (pinfunction "2_2") (pintype "passive"))
      (node (ref "R15") (pin "1") (pinfunction "1_1") (pintype "passive"))
      (node (ref "R2") (pin "2") (pinfunction "2_2") (pintype "passive"))
    )
    (net (code "23") (name "MAINCURRENT") (class "Default")
      (node (ref "Q1") (pin "24") (pinfunction "PC1_24") (pintype "bidirectional"))
      (node (ref "R9") (pin "2") (pinfunction "2_2") (pintype "passive"))
    )
    (net (code "24") (name "Net-(J1-2)") (class "Default")
      (node (ref "J1") (pin "P$2") (pinfunction "2_P$2") (pintype "bidirectional"))
      (node (ref "Q1") (pin "1") (pinfunction "PC6_1") (pintype "bidirectional"))
      (node (ref "R1") (pin "2") (pinfunction "2_2") (pintype "passive"))
    )
    (net (code "25") (name "Net-(J13-1-TRANS+)") (class "Default")
      (node (ref "J13") (pin "1") (pinfunction "1-TRANS+_1") (pintype "bidirectional"))
      (node (ref "Q2") (pin "5") (pinfunction "Y_5") (pintype "bidirectional"))
      (node (ref "R5") (pin "2") (pinfunction "2_2") (pintype "passive"))
    )
    (net (code "26") (name "Net-(J13-2-TRANS-)") (class "Default")
      (node (ref "J13") (pin "2") (pinfunction "2-TRANS-_2") (pintype "bidirectional"))
      (node (ref "Q2") (pin "6") (pinfunction "Z_6") (pintype "bidirectional"))
      (node (ref "R5") (pin "1") (pinfunction "1_1") (pintype "passive"))
    )
    (net (code "27") (name "Net-(J13-3+RECEIVE+)") (class "Default")
      (node (ref "J13") (pin "3") (pinfunction "3+RECEIVE+_3") (pintype "bidirectional"))
      (node (ref "Q2") (pin "8") (pinfunction "A_8") (pintype "bidirectional"))
      (node (ref "R6") (pin "1") (pinfunction "1_1") (pintype "passive"))
    )
    (net (code "28") (name "Net-(J13-6-RECEIVE-)") (class "Default")
      (node (ref "J13") (pin "6") (pinfunction "6-RECEIVE-_6") (pintype "bidirectional"))
      (node (ref "Q2") (pin "7") (pinfunction "B_7") (pintype "bidirectional"))
      (node (ref "R6") (pin "2") (pinfunction "2_2") (pintype "passive"))
    )
    (net (code "29") (name "Net-(Q1-AREF)") (class "Default")
      (node (ref "C5") (pin "1") (pinfunction "1_1") (pintype "passive"))
      (node (ref "Q1") (pin "21") (pinfunction "AREF_21") (pintype "bidirectional"))
    )
    (net (code "30") (name "Net-(Q1-PC2)") (class "Default")
      (node (ref "C17") (pin "1") (pinfunction "1_1") (pintype "passive"))
      (node (ref "Q1") (pin "25") (pinfunction "PC2_25") (pintype "bidirectional"))
      (node (ref "R7") (pin "2") (pinfunction "2_2") (pintype "passive"))
    )
    (net (code "31") (name "Net-(Q1-PD0)") (class "Default")
      (node (ref "Q1") (pin "2") (pinfunction "PD0_2") (pintype "bidirectional"))
      (node (ref "Q2") (pin "2") (pinfunction "R_2") (pintype "bidirectional"))
    )
    (net (code "32") (name "Net-(Q1-PD1)") (class "Default")
      (node (ref "Q1") (pin "3") (pinfunction "PD1_3") (pintype "bidirectional"))
      (node (ref "Q2") (pin "3") (pinfunction "D_3") (pintype "bidirectional"))
    )
    (net (code "33") (name "Net-(Q1-PD6)") (class "Default")
      (node (ref "Q1") (pin "12") (pinfunction "PD6_12") (pintype "bidirectional"))
      (node (ref "R8") (pin "2") (pinfunction "2_2") (pintype "passive"))
    )
    (net (code "34") (name "Net-(Q1-XTAL1)") (class "Default")
      (node (ref "C1") (pin "2") (pinfunction "2_2") (pintype "passive"))
      (node (ref "Q1") (pin "9") (pinfunction "XTAL1_9") (pintype "bidirectional"))
      (node (ref "X1") (pin "P$2") (pinfunction "2_P$2") (pintype "passive"))
    )
    (net (code "35") (name "Net-(Q1-XTAL2)") (class "Default")
      (node (ref "C2") (pin "2") (pinfunction "2_2") (pintype "passive"))
      (node (ref "Q1") (pin "10") (pinfunction "XTAL2_10") (pintype "bidirectional"))
      (node (ref "X1") (pin "P$1") (pinfunction "1_P$1") (pintype "passive"))
    )
    (net (code "36") (name "Net-(Q3-G)") (class "Default")
      (node (ref "Q3") (pin "1") (pinfunction "G_1") (pintype "bidirectional"))
      (node (ref "R4") (pin "2") (pinfunction "2_2") (pintype "passive"))
    )
    (net (code "37") (name "Net-(Q4-A)") (class "Default")
      (node (ref "Q4") (pin "10") (pinfunction "A_10") (pintype "bidirectional"))
      (node (ref "R17") (pin "2") (pinfunction "2_2") (pintype "passive"))
    )
    (net (code "38") (name "Net-(Q4-B)") (class "Default")
      (node (ref "Q4") (pin "11") (pinfunction "B_11") (pintype "bidirectional"))
      (node (ref "R18") (pin "2") (pinfunction "2_2") (pintype "passive"))
    )
    (net (code "39") (name "Net-(Q7-D)") (class "Default")
      (node (ref "Q7") (pin "2") (pinfunction "D_2") (pintype "bidirectional"))
      (node (ref "Q7") (pin "4") (pinfunction "P$1_4") (pintype "bidirectional"))
      (node (ref "Q8") (pin "4") (pinfunction "P$1_4") (pintype "bidirectional"))
    )
    (net (code "40") (name "Net-(Q9-VIOUT7)") (class "Default")
      (node (ref "Q9") (pin "7") (pinfunction "VIOUT7_7") (pintype "bidirectional"))
      (node (ref "R10") (pin "1") (pinfunction "1_1") (pintype "passive"))
    )
    (net (code "41") (name "Net-(Q20-+IN)") (class "Default")
      (node (ref "Q20") (pin "8") (pinfunction "+IN_8") (pintype "bidirectional"))
      (node (ref "R15") (pin "SENSE2") (pinfunction "SENSE2_SENSE2") (pintype "bidirectional"))
    )
    (net (code "42") (name "Net-(Q20--IN)") (class "Default")
      (node (ref "Q20") (pin "1") (pinfunction "-IN_1") (pintype "bidirectional"))
      (node (ref "R15") (pin "SENSE1") (pinfunction "SENSE1_SENSE1") (pintype "bidirectional"))
    )
    (net (code "43") (name "Net-(Q20-OUT)") (class "Default")
      (node (ref "Q20") (pin "5") (pinfunction "OUT_5") (pintype "bidirectional"))
      (node (ref "R14") (pin "1") (pinfunction "1_1") (pintype "passive"))
    )
    (net (code "44") (name "Net-(R14-Pad2)") (class "Default")
      (node (ref "R14") (pin "2") (pinfunction "2_2") (pintype "passive"))
      (node (ref "R9") (pin "1") (pinfunction "1_1") (pintype "passive"))
    )
    (net (code "45") (name "Net-(R19-Pad1)") (class "Default")
      (node (ref "R19") (pin "1") (pinfunction "1_1") (pintype "passive"))
      (node (ref "R20") (pin "2") (pinfunction "2_2") (pintype "passive"))
    )
    (net (code "46") (name "PANIC") (class "Default")
      (node (ref "J12") (pin "2") (pinfunction "2_2") (pintype "passive"))
      (node (ref "Q1") (pin "27") (pinfunction "PC4_27") (pintype "bidirectional"))
      (node (ref "R12") (pin "1") (pinfunction "1_1") (pintype "passive"))
    )
    (net (code "47") (name "QBATTERY1") (class "Default")
      (node (ref "Q10") (pin "7") (pinfunction "HO_7") (pintype "bidirectional"))
      (node (ref "Q8") (pin "1") (pinfunction "G_1") (pintype "bidirectional"))
    )
    (net (code "48") (name "QBATTERY2") (class "Default")
      (node (ref "Q11") (pin "7") (pinfunction "HO_7") (pintype "bidirectional"))
      (node (ref "Q7") (pin "1") (pinfunction "G_1") (pintype "bidirectional"))
    )
    (net (code "49") (name "S1_HIGH") (class "Default")
      (node (ref "C15") (pin "1") (pinfunction "1_1") (pintype "passive"))
      (node (ref "P2") (pin "4") (pinfunction "+VO_4") (pintype "output"))
      (node (ref "Q10") (pin "8") (pinfunction "VB_8") (pintype "bidirectional"))
    )
    (net (code "50") (name "S2_HIGH") (class "Default")
      (node (ref "C16") (pin "1") (pinfunction "1_1") (pintype "passive"))
      (node (ref "P3") (pin "4") (pinfunction "+VO_4") (pintype "output"))
      (node (ref "Q11") (pin "8") (pinfunction "VB_8") (pintype "bidirectional"))
    )
    (net (code "51") (name "S_BATTERY") (class "Default")
      (node (ref "Q1") (pin "15") (pinfunction "PB1_15") (pintype "bidirectional"))
      (node (ref "Q10") (pin "2") (pinfunction "IN_2") (pintype "bidirectional"))
      (node (ref "Q11") (pin "2") (pinfunction "IN_2") (pintype "bidirectional"))
    )
    (net (code "52") (name "S_BUCK") (class "Default")
      (node (ref "Q1") (pin "16") (pinfunction "PB2_16") (pintype "bidirectional"))
      (node (ref "Q6") (pin "2") (pinfunction "IN_2") (pintype "bidirectional"))
    )
    (net (code "53") (name "TEMP") (class "Default")
      (node (ref "Q1") (pin "28") (pinfunction "PC5_28") (pintype "bidirectional"))
      (node (ref "Q4") (pin "17") (pinfunction "YCOM_17") (pintype "bidirectional"))
    )
    (net (code "54") (name "TEMP1") (class "Default")
      (node (ref "J2") (pin "4") (pinfunction "4_4") (pintype "passive"))
      (node (ref "Q4") (pin "23") (pinfunction "Y1_23") (pintype "bidirectional"))
    )
    (net (code "55") (name "TEMP2") (class "Default")
      (node (ref "J3") (pin "4") (pinfunction "4_4") (pintype "passive"))
      (node (ref "Q4") (pin "22") (pinfunction "Y2_22") (pintype "bidirectional"))
    )
    (net (code "56") (name "TEMP3") (class "Default")
      (node (ref "J4") (pin "4") (pinfunction "4_4") (pintype "passive"))
      (node (ref "Q4") (pin "21") (pinfunction "Y3_21") (pintype "bidirectional"))
    )
    (net (code "57") (name "TEMP4") (class "Default")
      (node (ref "J5") (pin "4") (pinfunction "4_4") (pintype "passive"))
      (node (ref "Q4") (pin "20") (pinfunction "Y4_20") (pintype "bidirectional"))
    )
    (net (code "58") (name "TEMP5") (class "Default")
      (node (ref "J6") (pin "4") (pinfunction "4_4") (pintype "passive"))
      (node (ref "Q4") (pin "19") (pinfunction "Y5_19") (pintype "bidirectional"))
    )
    (net (code "59") (name "TEMP6") (class "Default")
      (node (ref "J7") (pin "4") (pinfunction "4_4") (pintype "passive"))
      (node (ref "Q4") (pin "18") (pinfunction "Y6_18") (pintype "bidirectional"))
    )
    (net (code "60") (name "TEMP7") (class "Default")
      (node (ref "J8") (pin "4") (pinfunction "4_4") (pintype "passive"))
      (node (ref "Q4") (pin "16") (pinfunction "Y7_16") (pintype "bidirectional"))
    )
    (net (code "61") (name "TEMP8") (class "Default")
      (node (ref "Q4") (pin "15") (pinfunction "Y8_15") (pintype "bidirectional"))
      (node (ref "Q5") (pin "2") (pinfunction "OUT_2") (pintype "bidirectional"))
    )
    (net (code "62") (name "VB") (class "Default")
      (node (ref "C13") (pin "1") (pinfunction "1_1") (pintype "passive"))
      (node (ref "P1") (pin "4") (pinfunction "+VO_4") (pintype "output"))
      (node (ref "Q6") (pin "8") (pinfunction "VB_8") (pintype "bidirectional"))
    )
    (net (code "63") (name "VIN") (class "Default")
      (node (ref "C27") (pin "1") (pinfunction "1_1") (pintype "passive"))
      (node (ref "Q4") (pin "2") (pinfunction "X8_2") (pintype "bidirectional"))
      (node (ref "R20") (pin "1") (pinfunction "1_1") (pintype "passive"))
      (node (ref "R21") (pin "2") (pinfunction "2_2") (pintype "passive"))
    )
    (net (code "64") (name "VOLTS") (class "Default")
      (node (ref "Q1") (pin "26") (pinfunction "PC3_26") (pintype "bidirectional"))
      (node (ref "Q4") (pin "1") (pinfunction "XCOM_1") (pintype "bidirectional"))
    )
    (net (code "65") (name "VOLTS1") (class "Default")
      (node (ref "J2") (pin "5") (pinfunction "5_5") (pintype "passive"))
      (node (ref "Q4") (pin "9") (pinfunction "X1_9") (pintype "bidirectional"))
    )
    (net (code "66") (name "VOLTS2") (class "Default")
      (node (ref "J3") (pin "5") (pinfunction "5_5") (pintype "passive"))
      (node (ref "Q4") (pin "8") (pinfunction "X2_8") (pintype "bidirectional"))
    )
    (net (code "67") (name "VOLTS3") (class "Default")
      (node (ref "J4") (pin "5") (pinfunction "5_5") (pintype "passive"))
      (node (ref "Q4") (pin "7") (pinfunction "X3_7") (pintype "bidirectional"))
    )
    (net (code "68") (name "VOLTS4") (class "Default")
      (node (ref "J5") (pin "5") (pinfunction "5_5") (pintype "passive"))
      (node (ref "Q4") (pin "6") (pinfunction "X4_6") (pintype "bidirectional"))
    )
    (net (code "69") (name "VOLTS5") (class "Default")
      (node (ref "J6") (pin "5") (pinfunction "5_5") (pintype "passive"))
      (node (ref "Q4") (pin "5") (pinfunction "X5_5") (pintype "bidirectional"))
    )
    (net (code "70") (name "VOLTS6") (class "Default")
      (node (ref "J7") (pin "5") (pinfunction "5_5") (pintype "passive"))
      (node (ref "Q4") (pin "4") (pinfunction "X6_4") (pintype "bidirectional"))
    )
    (net (code "71") (name "VOLTS7") (class "Default")
      (node (ref "J8") (pin "5") (pinfunction "5_5") (pintype "passive"))
      (node (ref "Q4") (pin "3") (pinfunction "X7_3") (pintype "bidirectional"))
    )
    (net (code "72") (name "VS") (class "Default")
      (node (ref "C13") (pin "2") (pinfunction "2_2") (pintype "passive"))
      (node (ref "D1") (pin "2") (pinfunction "C1_2") (pintype "bidirectional"))
      (node (ref "D1") (pin "4") (pinfunction "C2_4") (pintype "bidirectional"))
      (node (ref "P1") (pin "3") (pinfunction "-VO_3") (pintype "output"))
      (node (ref "Q3") (pin "3") (pinfunction "S_3") (pintype "bidirectional"))
      (node (ref "Q6") (pin "6") (pinfunction "VS_6") (pintype "bidirectional"))
      (node (ref "Q9") (pin "3") (pinfunction "IP3-_3") (pintype "bidirectional"))
      (node (ref "Q9") (pin "4") (pinfunction "IP4-_4") (pintype "bidirectional"))
    )
    (net (code "73") (name "V_MAIN") (class "Default")
      (node (ref "C12") (pin "1") (pinfunction "1_1") (pintype "passive"))
      (node (ref "Q1") (pin "23") (pinfunction "PC0_23") (pintype "bidirectional"))
      (node (ref "R2") (pin "1") (pinfunction "1_1") (pintype "passive"))
      (node (ref "R3") (pin "2") (pinfunction "2_2") (pintype "passive"))
    )
    (net (code "74") (name "unconnected-(H1-Pad1)") (class "Default")
      (node (ref "H1") (pin "1") (pinfunction "1_1") (pintype "passive"))
    )
    (net (code "75") (name "unconnected-(H2-Pad1)") (class "Default")
      (node (ref "H2") (pin "1") (pinfunction "1_1") (pintype "passive"))
    )
    (net (code "76") (name "unconnected-(H3-Pad1)") (class "Default")
      (node (ref "H3") (pin "1") (pinfunction "1_1") (pintype "passive"))
    )
    (net (code "77") (name "unconnected-(J13-4-DC+-Pad4)") (class "Default")
      (node (ref "J13") (pin "4") (pinfunction "4-DC+_4") (pintype "bidirectional"))
    )
    (net (code "78") (name "unconnected-(J13-5-DC++-Pad5)") (class "Default")
      (node (ref "J13") (pin "5") (pinfunction "5-DC++_5") (pintype "bidirectional"))
    )
    (net (code "79") (name "unconnected-(Q8-D-Pad2)") (class "Default")
      (node (ref "Q8") (pin "2") (pinfunction "D_2") (pintype "bidirectional"))
    )
    (net (code "80") (name "unconnected-(Q9-FAULT6-Pad6)") (class "Default")
      (node (ref "Q9") (pin "6") (pinfunction "FAULT6_6") (pintype "bidirectional"))
    )
  )
)
